# main.net
KiCad netlist of a schematic drawn in Altium Designer
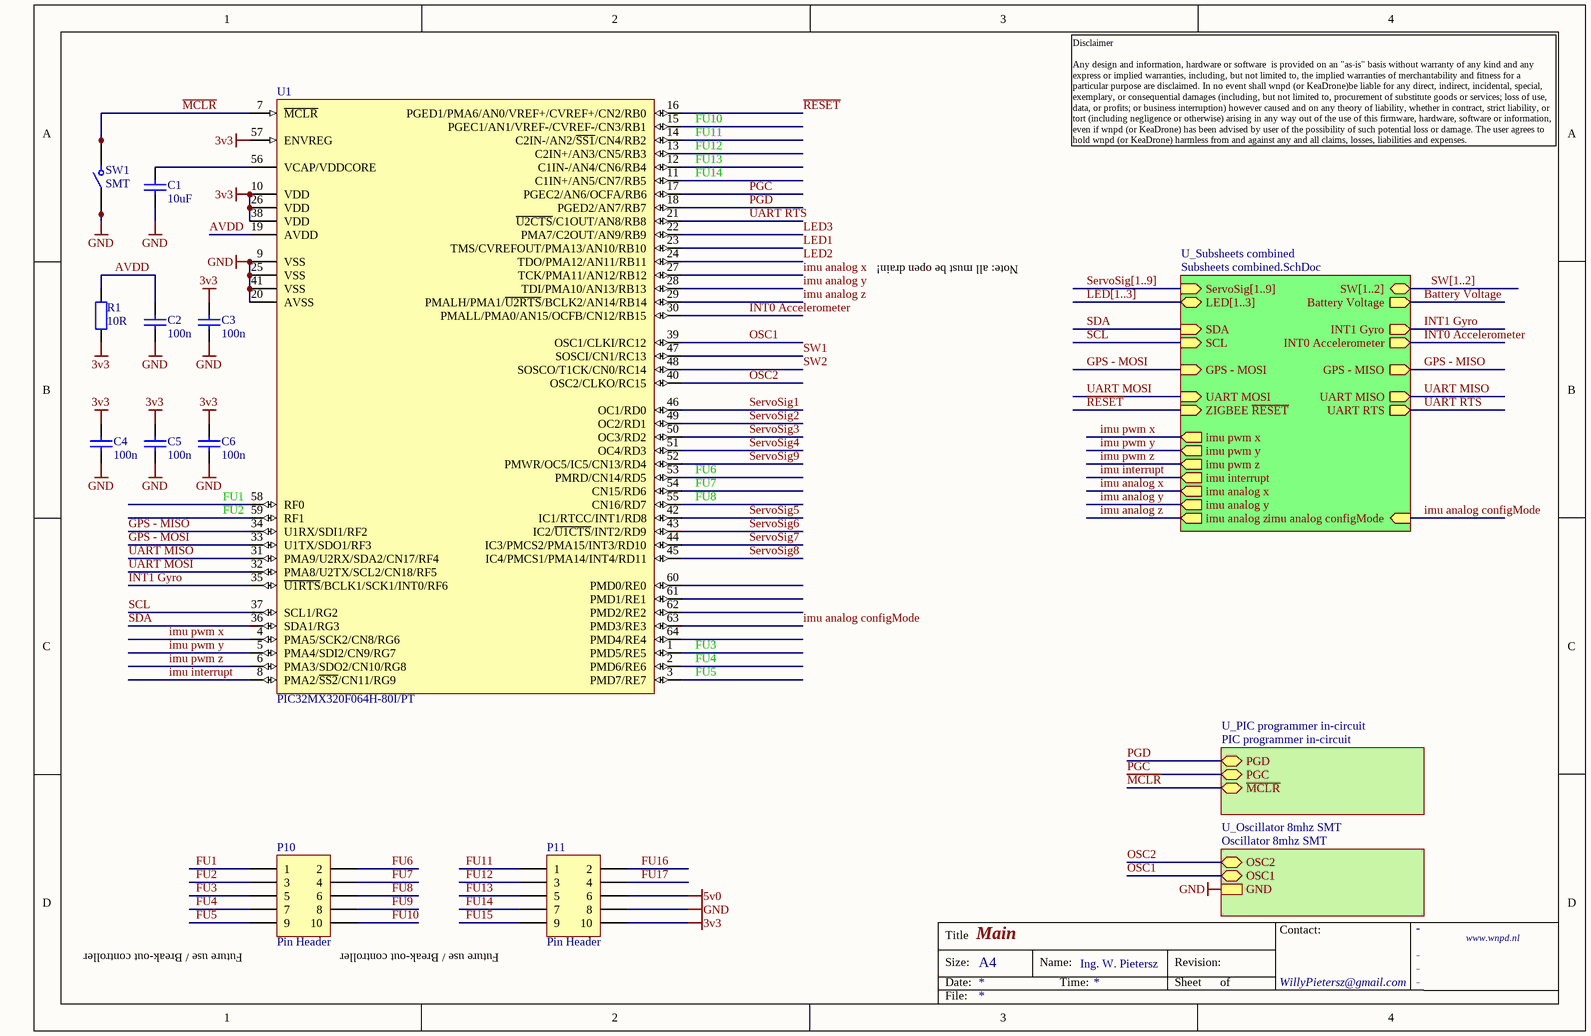
[diagram p0: main.SchDoc]

(export (version "E")
  (design (tool "Eeschema 10.0.6"))
  (components
    (comp (ref "C1")
      (value "10uF")
      (footprint "C1206")
      (fields
        (field (name "VOLTAGE") "10V")
        (field (name "TOLERANCE") "0.1")
        (field (name "AUTHOR") "Willem Pietersz")
      )
      (libsource (lib "OurDb") (part "cap_NonPolar"))
    )
    (comp (ref "C2")
      (value "100n")
      (footprint "C0805")
      (fields (field (name "TOLERANCE") "0.1") (field (name "AUTHOR") "Willy Pietersz"))
      (libsource (lib "OurDb") (part "cap_NonPolar"))
    )
    (comp (ref "C3")
      (value "100n")
      (footprint "C0805")
      (fields (field (name "TOLERANCE") "0.1") (field (name "AUTHOR") "Willy Pietersz"))
      (libsource (lib "OurDb") (part "cap_NonPolar"))
    )
    (comp (ref "C4")
      (value "100n")
      (footprint "C0805")
      (fields (field (name "TOLERANCE") "0.1") (field (name "AUTHOR") "Willy Pietersz"))
      (libsource (lib "OurDb") (part "cap_NonPolar"))
    )
    (comp (ref "C5")
      (value "100n")
      (footprint "C0805")
      (fields (field (name "TOLERANCE") "0.1") (field (name "AUTHOR") "Willy Pietersz"))
      (libsource (lib "OurDb") (part "cap_NonPolar"))
    )
    (comp (ref "C6")
      (value "100n")
      (footprint "C0805")
      (fields (field (name "TOLERANCE") "0.1") (field (name "AUTHOR") "Willy Pietersz"))
      (libsource (lib "OurDb") (part "cap_NonPolar"))
    )
    (comp (ref "P10")
      (value "Pin Header")
      (footprint "PH2x5_2.54")
      (description "Header, 5-Pin, Dual row")
      (fields (field (name "PART NUMBER") "PH2x5") (field (name "AUTHOR") "Willy Pietersz"))
      (libsource (lib "OurDb") (part "Con2x5"))
    )
    (comp (ref "P11")
      (value "Pin Header")
      (footprint "PH2x5_2.54")
      (description "Header, 5-Pin, Dual row")
      (fields (field (name "PART NUMBER") "PH2x5") (field (name "AUTHOR") "Willy Pietersz"))
      (libsource (lib "OurDb") (part "Con2x5"))
    )
    (comp (ref "R1")
      (value "10R")
      (footprint "R0805")
      (description "Resistor")
      (fields
        (field (name "POWER") "0.25W")
        (field (name "TOLERANCE") "0.05")
        (field (name "PUBLISHER") "Altium Limited")
        (field (name "AUTHOR") "Willy Pietersz")
      )
      (libsource (lib "OurDb") (part "RESISTOR"))
    )
    (comp (ref "SW1")
      (value "SMT")
      (footprint "SWITCH TACT")
      (description "Switch")
      (fields
        (field (name "PART NUMBER") "Pushbutton TACT")
        (field (name "VOLTAGE") "42")
        (field (name "AUTHOR") "Willem Pietersz")
      )
      (libsource (lib "OurDb") (part "SW-TACT"))
    )
    (comp (ref "U1")
      (value "PIC32MX320F064H-80I/PT")
      (footprint "TQFP-PT64_N")
      (description "High Performance 80 MHz MIPS-Based 32-Bit Flash Microcontroller, 64KB Program Memory, 64-pin TQFP")
      (fields (field (name "PUBLISHER") "Altium Limited"))
      (libsource (lib "Microchip Microcontroller 32-Bit PIC32") (part "PIC32MX320F064H-80I/PT"))
    )
  )
  (nets
    (net (code "1") (name "/AVDD") (class "Default")
      (node (ref "C2") (pin "2") (pinfunction "2_2") (pintype "passive"))
      (node (ref "R1") (pin "1") (pinfunction "1_1") (pintype "passive"))
      (node (ref "U1") (pin "19") (pinfunction "AVDD_19") (pintype "power_in"))
    )
    (net (code "3") (name "/FU1") (class "Default")
      (node (ref "P10") (pin "1") (pinfunction "1_1") (pintype "passive"))
      (node (ref "U1") (pin "58") (pinfunction "RF0_58") (pintype "bidirectional"))
    )
    (net (code "4") (name "/FU2") (class "Default")
      (node (ref "P10") (pin "3") (pinfunction "3_3") (pintype "passive"))
      (node (ref "U1") (pin "59") (pinfunction "RF1_59") (pintype "bidirectional"))
    )
    (net (code "5") (name "/FU3") (class "Default")
      (node (ref "P10") (pin "5") (pinfunction "5_5") (pintype "passive"))
      (node (ref "U1") (pin "1") (pinfunction "PMD5/RE5_1") (pintype "bidirectional"))
    )
    (net (code "6") (name "/FU4") (class "Default")
      (node (ref "P10") (pin "7") (pinfunction "7_7") (pintype "passive"))
      (node (ref "U1") (pin "2") (pinfunction "PMD6/RE6_2") (pintype "bidirectional"))
    )
    (net (code "7") (name "/FU5") (class "Default")
      (node (ref "P10") (pin "9") (pinfunction "9_9") (pintype "passive"))
      (node (ref "U1") (pin "3") (pinfunction "PMD7/RE7_3") (pintype "bidirectional"))
    )
    (net (code "8") (name "/FU6") (class "Default")
      (node (ref "P10") (pin "2") (pinfunction "2_2") (pintype "passive"))
      (node (ref "U1") (pin "53") (pinfunction "PMRD/CN14/RD5_53") (pintype "bidirectional"))
    )
    (net (code "9") (name "/FU7") (class "Default")
      (node (ref "P10") (pin "4") (pinfunction "4_4") (pintype "passive"))
      (node (ref "U1") (pin "54") (pinfunction "CN15/RD6_54") (pintype "bidirectional"))
    )
    (net (code "10") (name "/FU8") (class "Default")
      (node (ref "P10") (pin "6") (pinfunction "6_6") (pintype "passive"))
      (node (ref "U1") (pin "55") (pinfunction "CN16/RD7_55") (pintype "bidirectional"))
    )
    (net (code "11") (name "/FU9") (class "Default")
      (node (ref "P10") (pin "8") (pinfunction "8_8") (pintype "passive"))
    )
    (net (code "12") (name "/FU10") (class "Default")
      (node (ref "P10") (pin "10") (pinfunction "10_10") (pintype "passive"))
      (node (ref "U1") (pin "15") (pinfunction "PGEC1/AN1/VREF-/CVREF-/CN3/RB1_15") (pintype "bidirectional"))
    )
    (net (code "13") (name "/FU11") (class "Default")
      (node (ref "P11") (pin "1") (pinfunction "1_1") (pintype "passive"))
      (node (ref "U1") (pin "14") (pinfunction "C2IN-/AN2/~{SS1}/CN4/RB2_14") (pintype "bidirectional"))
    )
    (net (code "14") (name "/FU12") (class "Default")
      (node (ref "P11") (pin "3") (pinfunction "3_3") (pintype "passive"))
      (node (ref "U1") (pin "13") (pinfunction "C2IN+/AN3/CN5/RB3_13") (pintype "bidirectional"))
    )
    (net (code "15") (name "/FU13") (class "Default")
      (node (ref "P11") (pin "5") (pinfunction "5_5") (pintype "passive"))
      (node (ref "U1") (pin "12") (pinfunction "C1IN-/AN4/CN6/RB4_12") (pintype "bidirectional"))
    )
    (net (code "16") (name "/FU14") (class "Default")
      (node (ref "P11") (pin "7") (pinfunction "7_7") (pintype "passive"))
      (node (ref "U1") (pin "11") (pinfunction "C1IN+/AN5/CN7/RB5_11") (pintype "bidirectional"))
    )
    (net (code "17") (name "/FU15") (class "Default")
      (node (ref "P11") (pin "9") (pinfunction "9_9") (pintype "passive"))
    )
    (net (code "18") (name "/FU16") (class "Default")
      (node (ref "P11") (pin "2") (pinfunction "2_2") (pintype "passive"))
    )
    (net (code "19") (name "/FU17") (class "Default")
      (node (ref "P11") (pin "4") (pinfunction "4_4") (pintype "passive"))
    )
    (net (code "20") (name "/GPS - MISO") (class "Default")
      (node (ref "U1") (pin "34") (pinfunction "U1RX/SDI1/RF2_34") (pintype "bidirectional"))
    )
    (net (code "21") (name "/GPS - MOSI") (class "Default")
      (node (ref "U1") (pin "33") (pinfunction "U1TX/SDO1/RF3_33") (pintype "bidirectional"))
    )
    (net (code "22") (name "/INT0 Accelerometer") (class "Default")
      (node (ref "U1") (pin "30") (pinfunction "PMALL/PMA0/AN15/OCFB/CN12/RB15_30") (pintype "bidirectional"))
    )
    (net (code "23") (name "/INT1 Gyro") (class "Default")
      (node (ref "U1") (pin "35") (pinfunction "~{U1RTS}/BCLK1/SCK1/INT0/RF6_35") (pintype "bidirectional"))
    )
    (net (code "24") (name "/LED1") (class "Default")
      (node (ref "U1") (pin "23") (pinfunction "TMS/CVREFOUT/PMA13/AN10/RB10_23") (pintype "bidirectional"))
    )
    (net (code "25") (name "/LED2") (class "Default")
      (node (ref "U1") (pin "24") (pinfunction "TDO/PMA12/AN11/RB11_24") (pintype "bidirectional"))
    )
    (net (code "26") (name "/LED3") (class "Default")
      (node (ref "U1") (pin "22") (pinfunction "PMA7/C2OUT/AN9/RB9_22") (pintype "bidirectional"))
    )
    (net (code "28") (name "/OSC1") (class "Default")
      (node (ref "U1") (pin "39") (pinfunction "OSC1/CLKI/RC12_39") (pintype "bidirectional"))
    )
    (net (code "29") (name "/OSC2") (class "Default")
      (node (ref "U1") (pin "40") (pinfunction "OSC2/CLKO/RC15_40") (pintype "bidirectional"))
    )
    (net (code "30") (name "/PGC") (class "Default")
      (node (ref "U1") (pin "17") (pinfunction "PGEC2/AN6/OCFA/RB6_17") (pintype "bidirectional"))
    )
    (net (code "31") (name "/PGD") (class "Default")
      (node (ref "U1") (pin "18") (pinfunction "PGED2/AN7/RB7_18") (pintype "bidirectional"))
    )
    (net (code "32") (name "/SCL") (class "Default")
      (node (ref "U1") (pin "37") (pinfunction "SCL1/RG2_37") (pintype "bidirectional"))
    )
    (net (code "33") (name "/SDA") (class "Default")
      (node (ref "U1") (pin "36") (pinfunction "SDA1/RG3_36") (pintype "bidirectional"))
    )
    (net (code "34") (name "/SW1") (class "Default")
      (node (ref "U1") (pin "47") (pinfunction "SOSCI/CN1/RC13_47") (pintype "bidirectional"))
    )
    (net (code "35") (name "/SW2") (class "Default")
      (node (ref "U1") (pin "48") (pinfunction "SOSCO/T1CK/CN0/RC14_48") (pintype "bidirectional"))
    )
    (net (code "37") (name "/ServoSig1") (class "Default")
      (node (ref "U1") (pin "46") (pinfunction "OC1/RD0_46") (pintype "bidirectional"))
    )
    (net (code "38") (name "/ServoSig2") (class "Default")
      (node (ref "U1") (pin "49") (pinfunction "OC2/RD1_49") (pintype "bidirectional"))
    )
    (net (code "39") (name "/ServoSig3") (class "Default")
      (node (ref "U1") (pin "50") (pinfunction "OC3/RD2_50") (pintype "bidirectional"))
    )
    (net (code "40") (name "/ServoSig4") (class "Default")
      (node (ref "U1") (pin "51") (pinfunction "OC4/RD3_51") (pintype "bidirectional"))
    )
    (net (code "41") (name "/ServoSig5") (class "Default")
      (node (ref "U1") (pin "42") (pinfunction "IC1/RTCC/INT1/RD8_42") (pintype "bidirectional"))
    )
    (net (code "42") (name "/ServoSig6") (class "Default")
      (node (ref "U1") (pin "43") (pinfunction "IC2/~{U1CTS}/INT2/RD9_43") (pintype "bidirectional"))
    )
    (net (code "43") (name "/ServoSig7") (class "Default")
      (node (ref "U1") (pin "44") (pinfunction "IC3/PMCS2/PMA15/INT3/RD10_44") (pintype "bidirectional"))
    )
    (net (code "44") (name "/ServoSig8") (class "Default")
      (node (ref "U1") (pin "45") (pinfunction "IC4/PMCS1/PMA14/INT4/RD11_45") (pintype "bidirectional"))
    )
    (net (code "45") (name "/ServoSig9") (class "Default")
      (node (ref "U1") (pin "52") (pinfunction "PMWR/OC5/IC5/CN13/RD4_52") (pintype "bidirectional"))
    )
    (net (code "47") (name "/UART MISO") (class "Default")
      (node (ref "U1") (pin "31") (pinfunction "PMA9/U2RX/SDA2/CN17/RF4_31") (pintype "bidirectional"))
    )
    (net (code "48") (name "/UART MOSI") (class "Default")
      (node (ref "U1") (pin "32") (pinfunction "PMA8/U2TX/SCL2/CN18/RF5_32") (pintype "bidirectional"))
    )
    (net (code "49") (name "/UART RTS") (class "Default")
      (node (ref "U1") (pin "21") (pinfunction "~{U2CTS}/C1OUT/AN8/RB8_21") (pintype "bidirectional"))
    )
    (net (code "50") (name "/imu analog configMode") (class "Default")
      (node (ref "U1") (pin "63") (pinfunction "PMD3/RE3_63") (pintype "bidirectional"))
    )
    (net (code "51") (name "/imu analog x") (class "Default")
      (node (ref "U1") (pin "27") (pinfunction "TCK/PMA11/AN12/RB12_27") (pintype "bidirectional"))
    )
    (net (code "52") (name "/imu analog y") (class "Default")
      (node (ref "U1") (pin "28") (pinfunction "TDI/PMA10/AN13/RB13_28") (pintype "bidirectional"))
    )
    (net (code "53") (name "/imu analog z") (class "Default")
      (node (ref "U1") (pin "29") (pinfunction "PMALH/PMA1/~{U2RTS}/BCLK2/AN14/RB14_29") (pintype "bidirectional"))
    )
    (net (code "54") (name "/imu interrupt") (class "Default")
      (node (ref "U1") (pin "8") (pinfunction "PMA2/~{SS2}/CN11/RG9_8") (pintype "bidirectional"))
    )
    (net (code "55") (name "/imu pwm x") (class "Default")
      (node (ref "U1") (pin "4") (pinfunction "PMA5/SCK2/CN8/RG6_4") (pintype "bidirectional"))
    )
    (net (code "56") (name "/imu pwm y") (class "Default")
      (node (ref "U1") (pin "5") (pinfunction "PMA4/SDI2/CN9/RG7_5") (pintype "bidirectional"))
    )
    (net (code "57") (name "/imu pwm z") (class "Default")
      (node (ref "U1") (pin "6") (pinfunction "PMA3/SDO2/CN10/RG8_6") (pintype "bidirectional"))
    )
    (net (code "58") (name "/~{MCLR}") (class "Default")
      (node (ref "SW1") (pin "2") (pintype "passive"))
      (node (ref "SW1") (pin "3") (pintype "passive"))
      (node (ref "U1") (pin "7") (pinfunction "~{MCLR}_7") (pintype "input"))
    )
    (net (code "59") (name "/~{RESET}") (class "Default")
      (node (ref "U1") (pin "16") (pinfunction "PGED1/PMA6/AN0/VREF+/CVREF+/CN2/RB0_16") (pintype "bidirectional"))
    )
    (net (code "60") (name "3v3") (class "Default")
      (node (ref "C3") (pin "2") (pinfunction "2_2") (pintype "passive"))
      (node (ref "C4") (pin "2") (pinfunction "2_2") (pintype "passive"))
      (node (ref "C5") (pin "2") (pinfunction "2_2") (pintype "passive"))
      (node (ref "C6") (pin "2") (pinfunction "2_2") (pintype "passive"))
      (node (ref "P11") (pin "10") (pinfunction "10_10") (pintype "passive"))
      (node (ref "R1") (pin "2") (pinfunction "2_2") (pintype "passive"))
      (node (ref "U1") (pin "10") (pinfunction "VDD_10") (pintype "power_in"))
      (node (ref "U1") (pin "26") (pinfunction "VDD_26") (pintype "power_in"))
      (node (ref "U1") (pin "38") (pinfunction "VDD_38") (pintype "power_in"))
      (node (ref "U1") (pin "57") (pinfunction "ENVREG_57") (pintype "input"))
    )
    (net (code "61") (name "5v0") (class "Default")
      (node (ref "P11") (pin "6") (pinfunction "6_6") (pintype "passive"))
    )
    (net (code "62") (name "GND") (class "Default")
      (node (ref "C1") (pin "1") (pinfunction "1_1") (pintype "passive"))
      (node (ref "C2") (pin "1") (pinfunction "1_1") (pintype "passive"))
      (node (ref "C3") (pin "1") (pinfunction "1_1") (pintype "passive"))
      (node (ref "C4") (pin "1") (pinfunction "1_1") (pintype "passive"))
      (node (ref "C5") (pin "1") (pinfunction "1_1") (pintype "passive"))
      (node (ref "C6") (pin "1") (pinfunction "1_1") (pintype "passive"))
      (node (ref "P11") (pin "8") (pinfunction "8_8") (pintype "passive"))
      (node (ref "SW1") (pin "1") (pintype "passive"))
      (node (ref "SW1") (pin "4") (pintype "passive"))
      (node (ref "U1") (pin "20") (pinfunction "AVSS_20") (pintype "power_in"))
      (node (ref "U1") (pin "25") (pinfunction "VSS_25") (pintype "power_in"))
      (node (ref "U1") (pin "41") (pinfunction "VSS_41") (pintype "power_in"))
      (node (ref "U1") (pin "9") (pinfunction "VSS_9") (pintype "power_in"))
    )
    (net (code "63") (name "Net-(U1-VCAP{slash}VDDCORE)") (class "Default")
      (node (ref "C1") (pin "2") (pinfunction "2_2") (pintype "passive"))
      (node (ref "U1") (pin "56") (pinfunction "VCAP/VDDCORE_56") (pintype "power_in"))
    )
    (net (code "64") (name "unconnected-(U1-PMD0{slash}RE0-Pad60)") (class "Default")
      (node (ref "U1") (pin "60") (pinfunction "PMD0/RE0_60") (pintype "bidirectional"))
    )
    (net (code "65") (name "unconnected-(U1-PMD1{slash}RE1-Pad61)") (class "Default")
      (node (ref "U1") (pin "61") (pinfunction "PMD1/RE1_61") (pintype "bidirectional"))
    )
    (net (code "66") (name "unconnected-(U1-PMD2{slash}RE2-Pad62)") (class "Default")
      (node (ref "U1") (pin "62") (pinfunction "PMD2/RE2_62") (pintype "bidirectional"))
    )
    (net (code "67") (name "unconnected-(U1-PMD4{slash}RE4-Pad64)") (class "Default")
      (node (ref "U1") (pin "64") (pinfunction "PMD4/RE4_64") (pintype "bidirectional"))
    )
  )
)
